# gydrodrive_encoder.net
KiCad netlist of a schematic drawn in Altium Designer
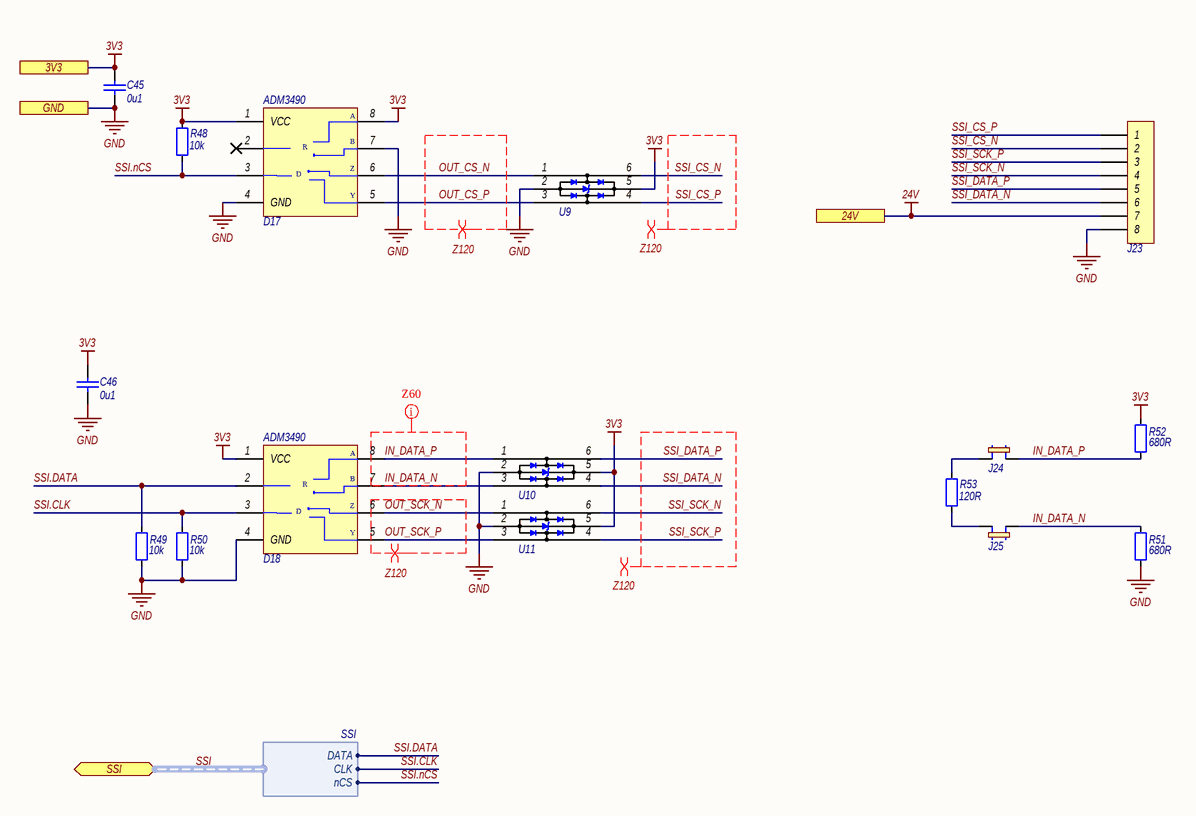
[diagram p0: gydrodrive_encoder.SchDoc]

(export (version "E")
  (design (tool "Eeschema 10.0.6"))
  (components
    (comp (ref "C45")
      (value "CAP_0805")
      (footprint "CAPC2012-0805M")
      (description "Конденсатор керамический, корпус 0805")
      (fields
        (field (name "CAPACITANCE") "0u1")
        (field (name "PART NUMBER") "CAPC_0805")
        (field (name "VOLTAGE") "50V")
      )
      (libsource (lib "StdLib") (part "CAP"))
    )
    (comp (ref "C46")
      (value "CAP_0805")
      (footprint "CAPC2012-0805M")
      (description "Конденсатор керамический, корпус 0805")
      (fields
        (field (name "CAPACITANCE") "0u1")
        (field (name "PART NUMBER") "CAPC_0805")
        (field (name "VOLTAGE") "50V")
      )
      (libsource (lib "StdLib") (part "CAP"))
    )
    (comp (ref "D17")
      (value "ADM3490")
      (footprint "SO8_M")
      (description "Дифференциальный приемопередатчик rs422")
      (libsource (lib "StdLib") (part "RS422_NOEN_SO8"))
    )
    (comp (ref "D18")
      (value "ADM3490")
      (footprint "SO8_M")
      (description "Дифференциальный приемопередатчик rs422")
      (libsource (lib "StdLib") (part "RS422_NOEN_SO8"))
    )
    (comp (ref "J23")
      (value "DG142V-5.08-08P")
      (footprint "DG142V-5.08-08P")
      (description "Клеммник 8-контактный, шаг 5.08 мм")
      (libsource (lib "StdLib") (part "PIN1x8"))
    )
    (comp (ref "J24")
      (value "PLS-2.54-2 JUMP")
      (footprint "PLS-2-2.54")
      (description "Разъем штыревой шаг 2.54 мм")
      (libsource (lib "") (part "PIN1x2_JUMP_1"))
    )
    (comp (ref "J25")
      (value "PLS-2.54-2 JUMP")
      (footprint "PLS-2-2.54")
      (description "Разъем штыревой шаг 2.54 мм")
      (libsource (lib "StdLib") (part "PIN1x2_JUMP"))
    )
    (comp (ref "R48")
      (value "RES_0805")
      (footprint "RESC2012-0805M")
      (description "Рез-р, корпус 0805")
      (fields
        (field (name "RESISTANCE") "10k")
        (field (name "PART NUMBER") "RESC_0805")
        (field (name "TOLERANCE") "5%")
      )
      (libsource (lib "StdLib") (part "RES"))
    )
    (comp (ref "R49")
      (value "RES_0805")
      (footprint "RESC2012-0805M")
      (description "Рез-р, корпус 0805")
      (fields
        (field (name "RESISTANCE") "10k")
        (field (name "PART NUMBER") "RESC_0805")
        (field (name "TOLERANCE") "5%")
      )
      (libsource (lib "StdLib") (part "RES"))
    )
    (comp (ref "R50")
      (value "RES_0805")
      (footprint "RESC2012-0805M")
      (description "Рез-р, корпус 0805")
      (fields
        (field (name "RESISTANCE") "10k")
        (field (name "PART NUMBER") "RESC_0805")
        (field (name "TOLERANCE") "5%")
      )
      (libsource (lib "StdLib") (part "RES"))
    )
    (comp (ref "R51")
      (value "RES_1206")
      (footprint "RESC3216-1206M")
      (description "Рез-р, корпус 1206")
      (fields
        (field (name "RESISTANCE") "680R")
        (field (name "PART NUMBER") "RESC_1206")
        (field (name "TOLERANCE") "5%")
      )
      (libsource (lib "") (part "RES_1"))
    )
    (comp (ref "R52")
      (value "RES_1206")
      (footprint "RESC3216-1206M")
      (description "Рез-р, корпус 1206")
      (fields
        (field (name "RESISTANCE") "680R")
        (field (name "PART NUMBER") "RESC_1206")
        (field (name "TOLERANCE") "5%")
      )
      (libsource (lib "StdLib") (part "RES"))
    )
    (comp (ref "R53")
      (value "RES_1206")
      (footprint "RESC3216-1206M")
      (description "Рез-р, корпус 1206")
      (fields
        (field (name "RESISTANCE") "120R")
        (field (name "PART NUMBER") "RESC_1206")
        (field (name "TOLERANCE") "5%")
      )
      (libsource (lib "StdLib") (part "RES"))
    )
    (comp (ref "U9")
      (value "USBLC6-2SC6")
      (footprint "SOT23-6AM")
      (description "Диодная сборка для защиты дифференциальной линии")
      (fields (field (name "VOLTAGE") "5.25V"))
      (libsource (lib "StdLib") (part "USBLC6-2SC6"))
    )
    (comp (ref "U10")
      (value "USBLC6-2SC6")
      (footprint "SOT23-6AM")
      (description "Диодная сборка для защиты дифференциальной линии")
      (fields (field (name "VOLTAGE") "5.25V"))
      (libsource (lib "StdLib") (part "USBLC6-2SC6"))
    )
    (comp (ref "U11")
      (value "USBLC6-2SC6")
      (footprint "SOT23-6AM")
      (description "Диодная сборка для защиты дифференциальной линии")
      (fields (field (name "VOLTAGE") "5.25V"))
      (libsource (lib "StdLib") (part "USBLC6-2SC6"))
    )
  )
  (nets
    (net (code "2") (name "/IN_DATA_N") (class "Default")
      (node (ref "D18") (pin "7") (pinfunction "B_7") (pintype "passive"))
      (node (ref "J25") (pin "1") (pinfunction "1_1") (pintype "passive"))
      (node (ref "R51") (pin "1") (pinfunction "1_1") (pintype "passive"))
      (node (ref "U10") (pin "3") (pinfunction "IO2_3") (pintype "passive"))
    )
    (net (code "3") (name "/IN_DATA_P") (class "Default")
      (node (ref "D18") (pin "8") (pinfunction "A_8") (pintype "passive"))
      (node (ref "J24") (pin "1") (pinfunction "1_1") (pintype "passive"))
      (node (ref "R52") (pin "1") (pinfunction "1_1") (pintype "passive"))
      (node (ref "U10") (pin "1") (pinfunction "IO1_1") (pintype "passive"))
    )
    (net (code "4") (name "/OUT_CS_N") (class "Default")
      (node (ref "D17") (pin "6") (pinfunction "Z_6") (pintype "passive"))
      (node (ref "U9") (pin "1") (pinfunction "IO1_1") (pintype "passive"))
    )
    (net (code "5") (name "/OUT_CS_P") (class "Default")
      (node (ref "D17") (pin "5") (pinfunction "Y_5") (pintype "passive"))
      (node (ref "U9") (pin "3") (pinfunction "IO2_3") (pintype "passive"))
    )
    (net (code "6") (name "/OUT_SCK_N") (class "Default")
      (node (ref "D18") (pin "6") (pinfunction "Z_6") (pintype "passive"))
      (node (ref "U11") (pin "1") (pinfunction "IO1_1") (pintype "passive"))
    )
    (net (code "7") (name "/OUT_SCK_P") (class "Default")
      (node (ref "D18") (pin "5") (pinfunction "Y_5") (pintype "passive"))
      (node (ref "U11") (pin "3") (pinfunction "IO2_3") (pintype "passive"))
    )
    (net (code "8") (name "/SSI.CLK") (class "Default")
      (node (ref "D18") (pin "3") (pinfunction "DI_3") (pintype "passive"))
      (node (ref "R50") (pin "2") (pinfunction "2_2") (pintype "passive"))
    )
    (net (code "9") (name "/SSI.DATA") (class "Default")
      (node (ref "D18") (pin "2") (pinfunction "2_2") (pintype "passive"))
      (node (ref "R49") (pin "2") (pinfunction "2_2") (pintype "passive"))
    )
    (net (code "10") (name "/SSI.nCS") (class "Default")
      (node (ref "D17") (pin "3") (pinfunction "DI_3") (pintype "passive"))
      (node (ref "R48") (pin "1") (pinfunction "1_1") (pintype "passive"))
    )
    (net (code "11") (name "/SSI_CS_N") (class "Default")
      (node (ref "J23") (pin "2") (pinfunction "2_2") (pintype "passive"))
      (node (ref "U9") (pin "6") (pinfunction "IO1_6") (pintype "passive"))
    )
    (net (code "12") (name "/SSI_CS_P") (class "Default")
      (node (ref "J23") (pin "1") (pinfunction "1_1") (pintype "passive"))
      (node (ref "U9") (pin "4") (pinfunction "IO2_4") (pintype "passive"))
    )
    (net (code "13") (name "/SSI_DATA_N") (class "Default")
      (node (ref "J23") (pin "6") (pinfunction "6_6") (pintype "passive"))
      (node (ref "U10") (pin "4") (pinfunction "IO2_4") (pintype "passive"))
    )
    (net (code "14") (name "/SSI_DATA_P") (class "Default")
      (node (ref "J23") (pin "5") (pinfunction "5_5") (pintype "passive"))
      (node (ref "U10") (pin "6") (pinfunction "IO1_6") (pintype "passive"))
    )
    (net (code "15") (name "/SSI_SCK_N") (class "Default")
      (node (ref "J23") (pin "4") (pinfunction "4_4") (pintype "passive"))
      (node (ref "U11") (pin "6") (pinfunction "IO1_6") (pintype "passive"))
    )
    (net (code "16") (name "/SSI_SCK_P") (class "Default")
      (node (ref "J23") (pin "3") (pinfunction "3_3") (pintype "passive"))
      (node (ref "U11") (pin "4") (pinfunction "IO2_4") (pintype "passive"))
    )
    (net (code "18") (name "3V3") (class "Default")
      (node (ref "C45") (pin "2") (pinfunction "2_2") (pintype "passive"))
      (node (ref "C46") (pin "2") (pinfunction "2_2") (pintype "passive"))
      (node (ref "D17") (pin "1") (pinfunction "VCC_1") (pintype "passive"))
      (node (ref "D17") (pin "8") (pinfunction "A_8") (pintype "passive"))
      (node (ref "D18") (pin "1") (pinfunction "VCC_1") (pintype "passive"))
      (node (ref "R48") (pin "2") (pinfunction "2_2") (pintype "passive"))
      (node (ref "R52") (pin "2") (pinfunction "2_2") (pintype "passive"))
      (node (ref "U10") (pin "5") (pinfunction "Vbus_5") (pintype "passive"))
      (node (ref "U11") (pin "5") (pinfunction "Vbus_5") (pintype "passive"))
      (node (ref "U9") (pin "5") (pinfunction "Vbus_5") (pintype "passive"))
    )
    (net (code "19") (name "24V") (class "Default")
      (node (ref "J23") (pin "7") (pinfunction "7_7") (pintype "passive"))
    )
    (net (code "20") (name "GND") (class "Default")
      (node (ref "C45") (pin "1") (pinfunction "1_1") (pintype "passive"))
      (node (ref "C46") (pin "1") (pinfunction "1_1") (pintype "passive"))
      (node (ref "D17") (pin "4") (pinfunction "GND_4") (pintype "passive"))
      (node (ref "D17") (pin "7") (pinfunction "B_7") (pintype "passive"))
      (node (ref "D18") (pin "4") (pinfunction "GND_4") (pintype "passive"))
      (node (ref "J23") (pin "8") (pinfunction "8_8") (pintype "passive"))
      (node (ref "R49") (pin "1") (pinfunction "1_1") (pintype "passive"))
      (node (ref "R50") (pin "1") (pinfunction "1_1") (pintype "passive"))
      (node (ref "R51") (pin "2") (pinfunction "2_2") (pintype "passive"))
      (node (ref "U10") (pin "2") (pinfunction "GND_2") (pintype "passive"))
      (node (ref "U11") (pin "2") (pinfunction "GND_2") (pintype "passive"))
      (node (ref "U9") (pin "2") (pinfunction "GND_2") (pintype "passive"))
    )
    (net (code "21") (name "Net-(J24-Pad2)") (class "Default")
      (node (ref "J24") (pin "2") (pinfunction "2_2") (pintype "passive"))
      (node (ref "R53") (pin "2") (pinfunction "2_2") (pintype "passive"))
    )
    (net (code "22") (name "Net-(J25-Pad2)") (class "Default")
      (node (ref "J25") (pin "2") (pinfunction "2_2") (pintype "passive"))
      (node (ref "R53") (pin "1") (pinfunction "1_1") (pintype "passive"))
    )
    (net (code "23") (name "unconnected-(D17-Pad2)") (class "Default")
      (node (ref "D17") (pin "2") (pinfunction "2_2") (pintype "passive+no_connect"))
    )
  )
)
